# PGA-103-Basic-preamp.net
KiCad netlist of a schematic drawn in EAGLE
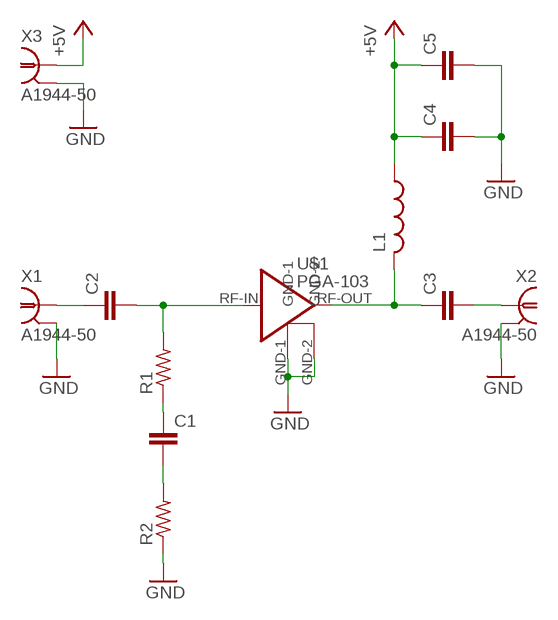
[diagram p0: schematic, sheet 1]

(export (version "E")
  (design (tool "Eeschema 10.0.6"))
  (components
    (comp (ref "C1")
      (value "C-EUC1206")
      (footprint "eagle-import:C1206")
      (libsource (lib "eagle-import") (part "C-EUC1206"))
    )
    (comp (ref "C2")
      (value "C-EUC1206")
      (footprint "eagle-import:C1206")
      (libsource (lib "eagle-import") (part "C-EUC1206"))
    )
    (comp (ref "C3")
      (value "C-EUC1206")
      (footprint "eagle-import:C1206")
      (libsource (lib "eagle-import") (part "C-EUC1206"))
    )
    (comp (ref "C4")
      (value "C-EUC1206")
      (footprint "eagle-import:C1206")
      (libsource (lib "eagle-import") (part "C-EUC1206"))
    )
    (comp (ref "C5")
      (value "C-EUC1206")
      (footprint "eagle-import:C1206")
      (libsource (lib "eagle-import") (part "C-EUC1206"))
    )
    (comp (ref "L1")
      (value "L-US0204/7")
      (footprint "eagle-import:0204_7")
      (libsource (lib "eagle-import") (part "L-US0204/7"))
    )
    (comp (ref "R1")
      (value "R-US_M1206")
      (footprint "eagle-import:M1206")
      (libsource (lib "eagle-import") (part "R-US_M1206"))
    )
    (comp (ref "R2")
      (value "R-US_M1206")
      (footprint "eagle-import:M1206")
      (libsource (lib "eagle-import") (part "R-US_M1206"))
    )
    (comp (ref "U$1")
      (value "PGA-103")
      (footprint "eagle-import:DF782")
      (libsource (lib "eagle-import") (part "PGA-103"))
    )
    (comp (ref "X1")
      (value "A1944-50")
      (footprint "eagle-import:A1944")
      (libsource (lib "eagle-import") (part "A1944-50"))
    )
    (comp (ref "X2")
      (value "A1944-50")
      (footprint "eagle-import:A1944")
      (libsource (lib "eagle-import") (part "A1944-50"))
    )
    (comp (ref "X3")
      (value "A1944-50")
      (footprint "eagle-import:A1944")
      (libsource (lib "eagle-import") (part "A1944-50"))
    )
  )
  (nets
    (net (code "1") (name "+5V") (class "Default")
      (node (ref "C4") (pin "1") (pinfunction "1_1") (pintype "passive"))
      (node (ref "C5") (pin "1") (pinfunction "1_1") (pintype "passive"))
      (node (ref "L1") (pin "1") (pinfunction "1_1") (pintype "passive"))
      (node (ref "X3") (pin "1") (pinfunction "1_1") (pintype "passive"))
    )
    (net (code "2") (name "GND") (class "Default")
      (node (ref "C4") (pin "2") (pinfunction "2_2") (pintype "passive"))
      (node (ref "C5") (pin "2") (pinfunction "2_2") (pintype "passive"))
      (node (ref "R2") (pin "1") (pinfunction "1_1") (pintype "passive"))
      (node (ref "U$1") (pin "GND-1") (pinfunction "GND-1_GND-1") (pintype "power_in"))
      (node (ref "U$1") (pin "GND-2") (pinfunction "GND-2_GND-2") (pintype "power_in"))
      (node (ref "X1") (pin "2") (pinfunction "2_2") (pintype "passive"))
      (node (ref "X1") (pin "3") (pinfunction "2_3") (pintype "passive"))
      (node (ref "X1") (pin "4") (pinfunction "2_4") (pintype "passive"))
      (node (ref "X1") (pin "5") (pinfunction "2_5") (pintype "passive"))
      (node (ref "X2") (pin "2") (pinfunction "2_2") (pintype "passive"))
      (node (ref "X2") (pin "3") (pinfunction "2_3") (pintype "passive"))
      (node (ref "X2") (pin "4") (pinfunction "2_4") (pintype "passive"))
      (node (ref "X2") (pin "5") (pinfunction "2_5") (pintype "passive"))
      (node (ref "X3") (pin "2") (pinfunction "2_2") (pintype "passive"))
      (node (ref "X3") (pin "3") (pinfunction "2_3") (pintype "passive"))
      (node (ref "X3") (pin "4") (pinfunction "2_4") (pintype "passive"))
      (node (ref "X3") (pin "5") (pinfunction "2_5") (pintype "passive"))
    )
    (net (code "3") (name "Net-(C1-Pad1)") (class "Default")
      (node (ref "C1") (pin "1") (pinfunction "1_1") (pintype "passive"))
      (node (ref "R1") (pin "1") (pinfunction "1_1") (pintype "passive"))
    )
    (net (code "4") (name "Net-(C1-Pad2)") (class "Default")
      (node (ref "C1") (pin "2") (pinfunction "2_2") (pintype "passive"))
      (node (ref "R2") (pin "2") (pinfunction "2_2") (pintype "passive"))
    )
    (net (code "5") (name "Net-(C2-Pad1)") (class "Default")
      (node (ref "C2") (pin "1") (pinfunction "1_1") (pintype "passive"))
      (node (ref "X1") (pin "1") (pinfunction "1_1") (pintype "passive"))
    )
    (net (code "6") (name "Net-(C2-Pad2)") (class "Default")
      (node (ref "C2") (pin "2") (pinfunction "2_2") (pintype "passive"))
      (node (ref "R1") (pin "2") (pinfunction "2_2") (pintype "passive"))
      (node (ref "U$1") (pin "RF-IN") (pinfunction "RF-IN_RF-IN") (pintype "input"))
    )
    (net (code "7") (name "Net-(C3-Pad1)") (class "Default")
      (node (ref "C3") (pin "1") (pinfunction "1_1") (pintype "passive"))
      (node (ref "L1") (pin "2") (pinfunction "2_2") (pintype "passive"))
      (node (ref "U$1") (pin "RF-OUT") (pinfunction "RF-OUT_RF-OUT") (pintype "output"))
    )
    (net (code "8") (name "Net-(C3-Pad2)") (class "Default")
      (node (ref "C3") (pin "2") (pinfunction "2_2") (pintype "passive"))
      (node (ref "X2") (pin "1") (pinfunction "1_1") (pintype "passive"))
    )
  )
)
